# CAN_controller.net
KiCad netlist of a schematic drawn in Altium Designer
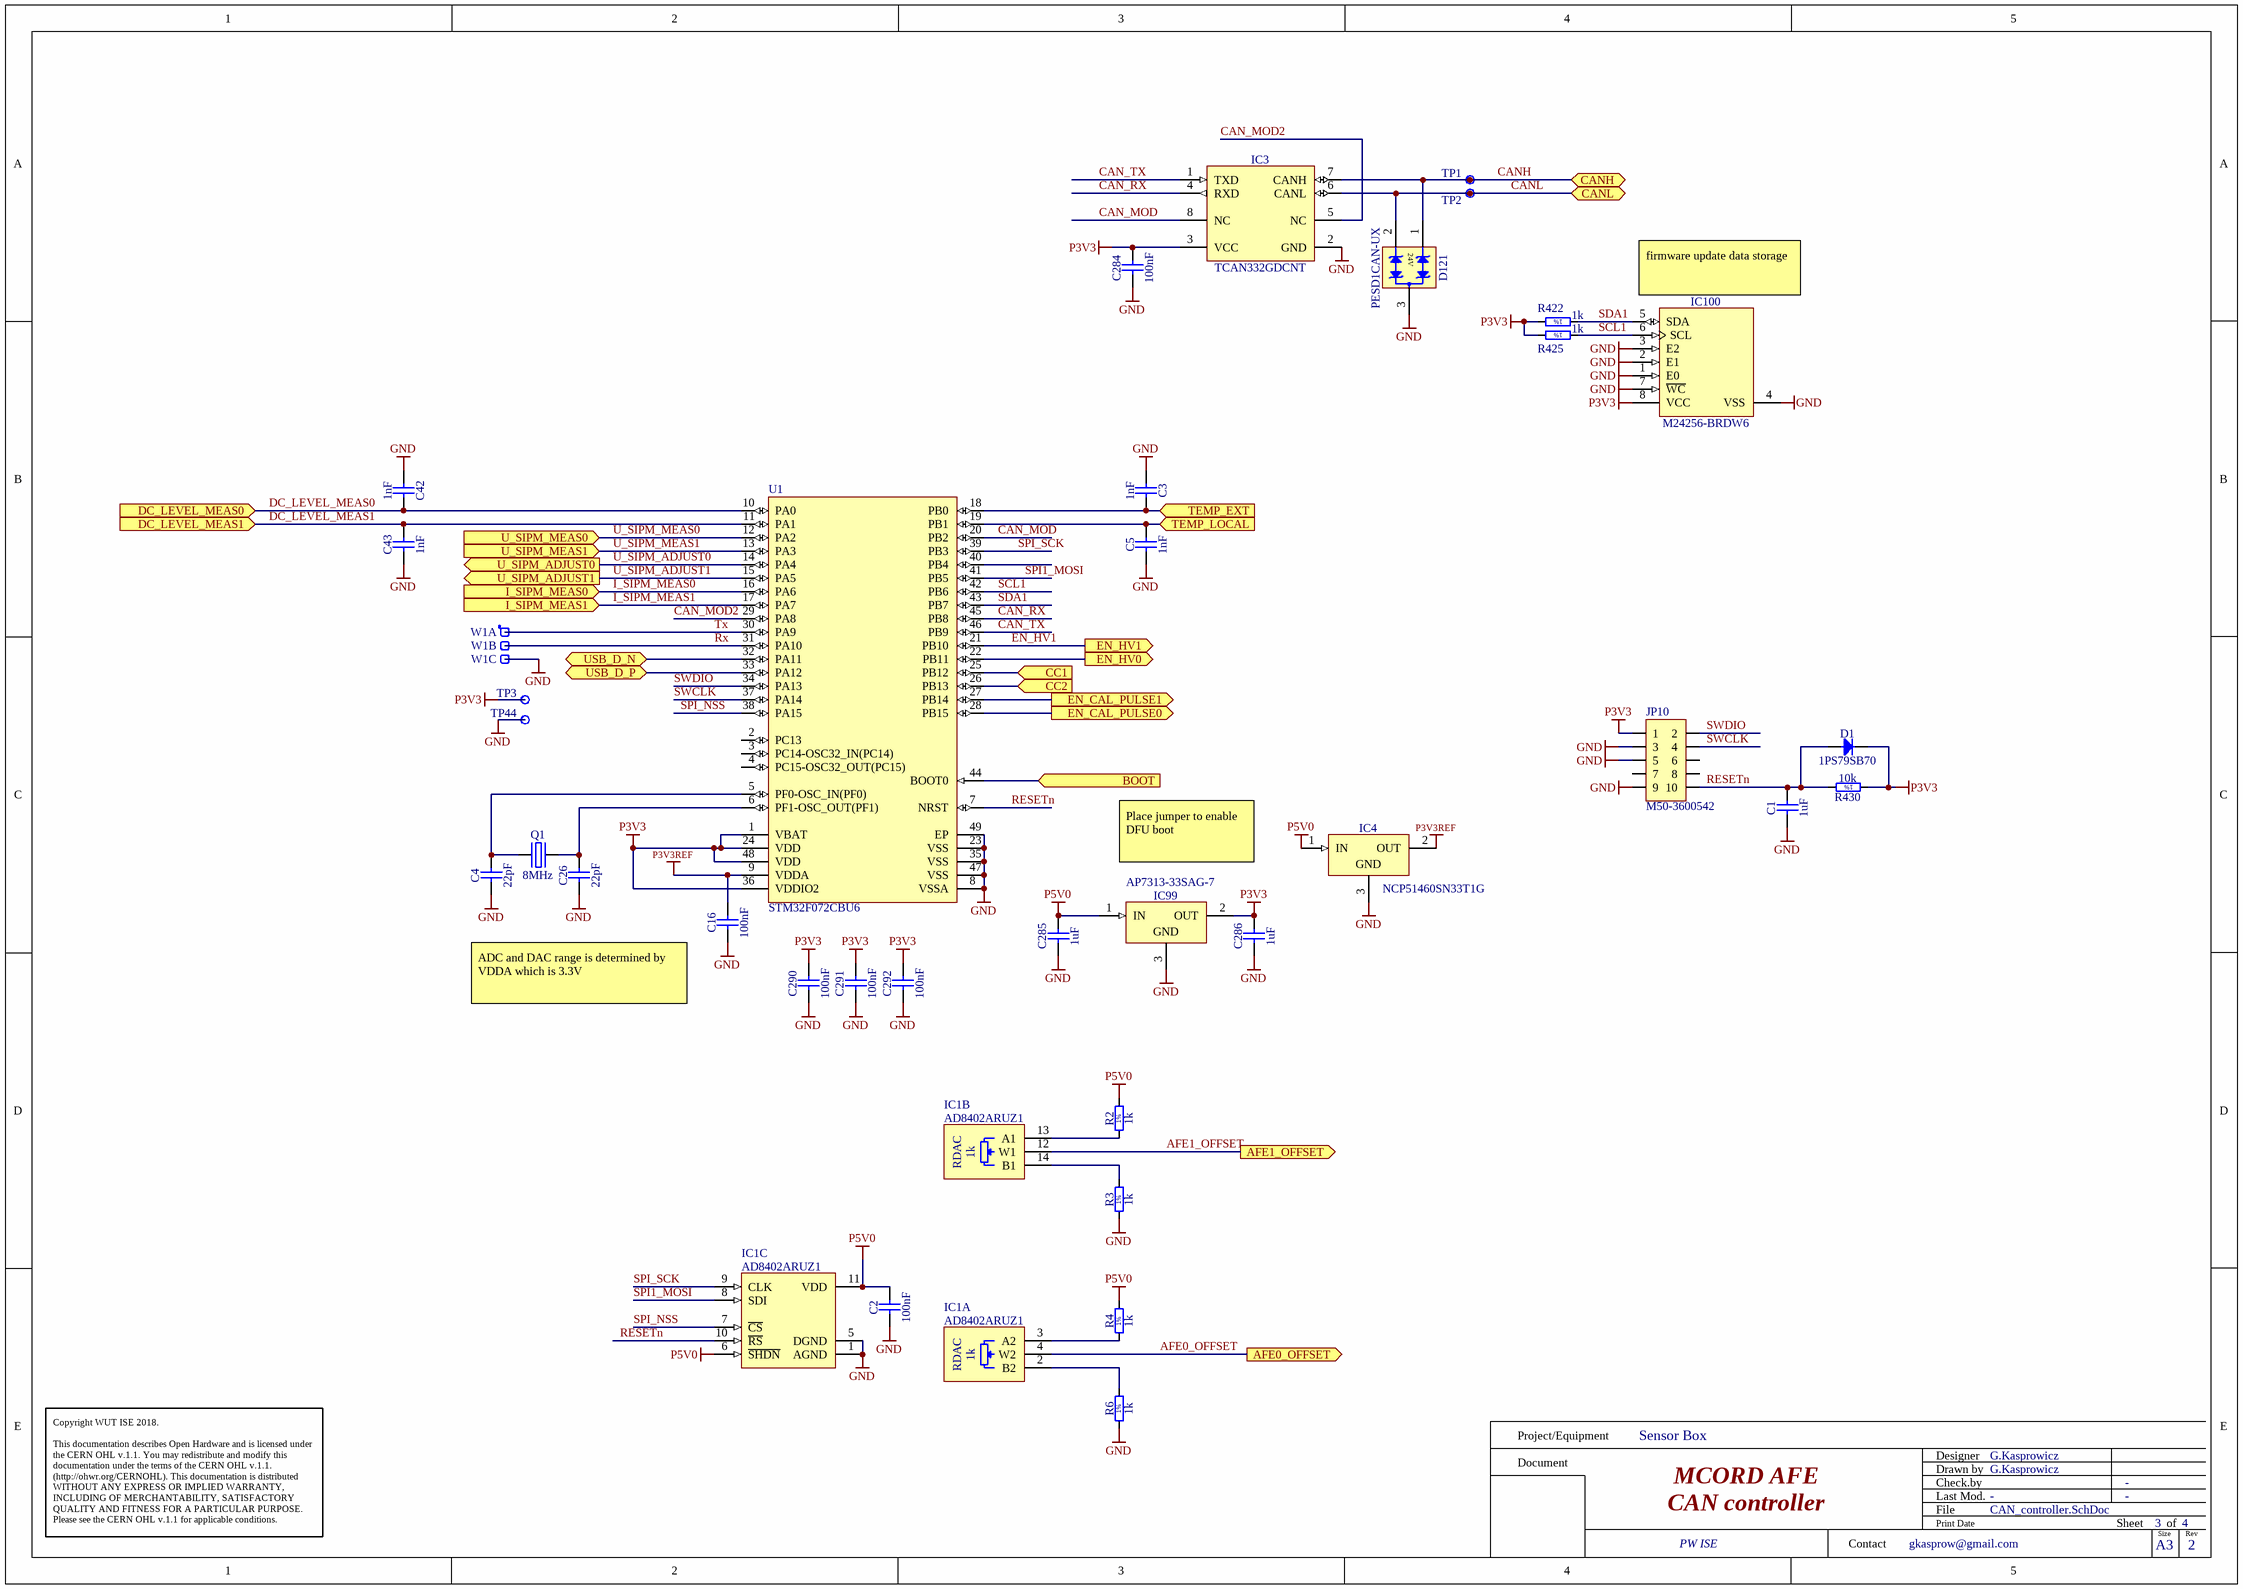
[diagram p0: CAN_controller.SchDoc]

(export (version "E")
  (design (tool "Eeschema 10.0.6"))
  (components
    (comp (ref "C1")
      (value "1uF")
      (footprint "CAPC1608X87N")
      (description "Non-polarised capacitor")
      (fields
        (field (name "PART NUMBER") "CC0603_1UF_16V_10%_X7R")
        (field (name "VOLTAGE") "16V")
        (field (name "AUTHOR") "CERN DEM JLC")
      )
      (libsource (lib "Capacitors") (part "Capacitor - non polarized"))
    )
    (comp (ref "C2")
      (value "100nF")
      (footprint "CAPC1005X55N")
      (description "Non-polarised capacitor")
      (fields
        (field (name "PART NUMBER") "CC0402_100NF_16V_10%_X7R")
        (field (name "VOLTAGE") "16V")
        (field (name "AUTHOR") "CERN DEM JLC")
      )
      (libsource (lib "Capacitors") (part "Capacitor - non polarized"))
    )
    (comp (ref "C3")
      (value "1nF")
      (footprint "CAPC1005X55N")
      (description "Non-polarised capacitor")
      (fields
        (field (name "PART NUMBER") "CC0402_1NF_50V_5%_C0G")
        (field (name "VOLTAGE") "50V")
        (field (name "AUTHOR") "CERN DEM BC")
      )
      (libsource (lib "Capacitors") (part "Capacitor - non polarized"))
    )
    (comp (ref "C4")
      (value "22pF")
      (footprint "CAPC1005X55N")
      (description "Non-polarised capacitor")
      (fields
        (field (name "PART NUMBER") "CC0402_22PF_50V_5%_C0G")
        (field (name "VOLTAGE") "50V")
        (field (name "AUTHOR") "CERN DEM JLC")
      )
      (libsource (lib "Capacitors") (part "Capacitor - non polarized"))
    )
    (comp (ref "C5")
      (value "1nF")
      (footprint "CAPC1005X55N")
      (description "Non-polarised capacitor")
      (fields
        (field (name "PART NUMBER") "CC0402_1NF_50V_5%_C0G")
        (field (name "VOLTAGE") "50V")
        (field (name "AUTHOR") "CERN DEM BC")
      )
      (libsource (lib "Capacitors") (part "Capacitor - non polarized"))
    )
    (comp (ref "C16")
      (value "100nF")
      (footprint "CAPC1005X55N")
      (description "Non-polarised capacitor")
      (fields
        (field (name "PART NUMBER") "CC0402_100NF_16V_10%_X7R")
        (field (name "VOLTAGE") "16V")
        (field (name "AUTHOR") "CERN DEM JLC")
      )
      (libsource (lib "Capacitors") (part "Capacitor - non polarized"))
    )
    (comp (ref "C26")
      (value "22pF")
      (footprint "CAPC1005X55N")
      (description "Non-polarised capacitor")
      (fields
        (field (name "PART NUMBER") "CC0402_22PF_50V_5%_C0G")
        (field (name "VOLTAGE") "50V")
        (field (name "AUTHOR") "CERN DEM JLC")
      )
      (libsource (lib "Capacitors") (part "Capacitor - non polarized"))
    )
    (comp (ref "C42")
      (value "1nF")
      (footprint "CAPC1005X55N")
      (description "Non-polarised capacitor")
      (fields
        (field (name "PART NUMBER") "CC0402_1NF_50V_5%_C0G")
        (field (name "VOLTAGE") "50V")
        (field (name "AUTHOR") "CERN DEM BC")
      )
      (libsource (lib "Capacitors") (part "Capacitor - non polarized"))
    )
    (comp (ref "C43")
      (value "1nF")
      (footprint "CAPC1005X55N")
      (description "Non-polarised capacitor")
      (fields
        (field (name "PART NUMBER") "CC0402_1NF_50V_5%_C0G")
        (field (name "VOLTAGE") "50V")
        (field (name "AUTHOR") "CERN DEM BC")
      )
      (libsource (lib "Capacitors") (part "Capacitor - non polarized"))
    )
    (comp (ref "C284")
      (value "100nF")
      (footprint "CAPC1005X55N")
      (description "Non-polarised capacitor")
      (fields
        (field (name "PART NUMBER") "CC0402_100NF_16V_10%_X7R")
        (field (name "VOLTAGE") "16V")
        (field (name "AUTHOR") "CERN DEM JLC")
      )
      (libsource (lib "Capacitors") (part "Capacitor - non polarized"))
    )
    (comp (ref "C285")
      (value "1uF")
      (footprint "CAPC1608X87N")
      (description "Non-polarised capacitor")
      (fields
        (field (name "PART NUMBER") "CC0603_1UF_16V_10%_X7R")
        (field (name "VOLTAGE") "16V")
        (field (name "AUTHOR") "CERN DEM JLC")
      )
      (libsource (lib "Capacitors") (part "Capacitor - non polarized"))
    )
    (comp (ref "C286")
      (value "1uF")
      (footprint "CAPC1608X87N")
      (description "Non-polarised capacitor")
      (fields
        (field (name "PART NUMBER") "CC0603_1UF_16V_10%_X7R")
        (field (name "VOLTAGE") "16V")
        (field (name "AUTHOR") "CERN DEM JLC")
      )
      (libsource (lib "Capacitors") (part "Capacitor - non polarized"))
    )
    (comp (ref "C290")
      (value "100nF")
      (footprint "CAPC1005X55N")
      (description "Non-polarised capacitor")
      (fields
        (field (name "PART NUMBER") "CC0402_100NF_16V_10%_X7R")
        (field (name "VOLTAGE") "16V")
        (field (name "AUTHOR") "CERN DEM JLC")
      )
      (libsource (lib "Capacitors") (part "Capacitor - non polarized"))
    )
    (comp (ref "C291")
      (value "100nF")
      (footprint "CAPC1005X55N")
      (description "Non-polarised capacitor")
      (fields
        (field (name "PART NUMBER") "CC0402_100NF_16V_10%_X7R")
        (field (name "VOLTAGE") "16V")
        (field (name "AUTHOR") "CERN DEM JLC")
      )
      (libsource (lib "Capacitors") (part "Capacitor - non polarized"))
    )
    (comp (ref "C292")
      (value "100nF")
      (footprint "CAPC1005X55N")
      (description "Non-polarised capacitor")
      (fields
        (field (name "PART NUMBER") "CC0402_100NF_16V_10%_X7R")
        (field (name "VOLTAGE") "16V")
        (field (name "AUTHOR") "CERN DEM JLC")
      )
      (libsource (lib "Capacitors") (part "Capacitor - non polarized"))
    )
    (comp (ref "D1")
      (value "1PS79SB70")
      (footprint "SODFL1608X65N")
      (description "Diode")
      (fields (field (name "VOLTAGE") "70V") (field (name "POWER") "70mA") (field (name "AUTHOR") "GK"))
      (libsource (lib "Diodes") (part "D_1PS79SB70"))
    )
    (comp (ref "D121")
      (value "PESD1CAN-UX")
      (footprint "SOT95P237X112-3N")
      (description "TVS Diode for CAN")
      (fields
        (field (name "VOLTAGE") "24V")
        (field (name "POWER") "400W")
        (field (name "AUTHOR") "CERN DEM JLC")
      )
      (libsource (lib "LIBRARY_SCH") (part "D_TVS_PESD1CAN"))
    )
    (comp (ref "IC1")
      (value "AD8402ARUZ1")
      (footprint "SOP65P640X120-14N")
      (description "2-Channel 1k Digital Potentiometer")
      (fields (field (name "MANUFACTURER") "ANALOG DEVICES") (field (name "AUTHOR") "GK"))
      (libsource (lib "ADC_DAC") (part "DAC_AD8402ARUZ1"))
    )
    (comp (ref "IC3")
      (value "TCAN332GDCNT")
      (footprint "SOT65P280X145-8N")
      (description "3.3V CAN Transceivers with CAN FD (Flexible Data Rate)")
      (fields (field (name "MANUFACTURER") "TEXAS INSTRUMENTS") (field (name "AUTHOR") "CERN DEM JLC"))
      (libsource (lib "ICs And Semiconductors") (part "TCAN332"))
    )
    (comp (ref "IC4")
      (value "NCP51460SN33T1G")
      (footprint "SOT95P240X110-3N")
      (description "3-Terminal Regulator 1=IN 2=OUT 3=GND")
      (fields (field (name "MANUFACTURER") "ON SEMICONDUCTOR") (field (name "AUTHOR") "CERN DEM MR"))
      (libsource (lib "ICs And Semiconductors") (part "REG3 1IN-2OUT-3GND"))
    )
    (comp (ref "IC99")
      (value "AP7313-33SAG-7")
      (footprint "SOT95P240X130-3N")
      (description "3-Terminal Regulator 1=IN 2=OUT 3=GND")
      (fields (field (name "MANUFACTURER") "DIODES INCORPORATED") (field (name "AUTHOR") "CERN DEM JLC"))
      (libsource (lib "ICs And Semiconductors") (part "REG3 1IN-2OUT-3GND"))
    )
    (comp (ref "IC100")
      (value "M24256-BRDW6")
      (footprint "SOP65P640X120-8N")
      (description "256-Kbit Serial I²C Bus EEPROM")
      (fields
        (field (name "PART NUMBER") "M24256-BRDW6P")
        (field (name "MANUFACTURER") "ST MICROELECTRONICS")
        (field (name "AUTHOR") "CERN DEM MR")
      )
      (libsource (lib "LIBRARY_SCH") (part "MEM_M24256-BRDW6P"))
    )
    (comp (ref "JP10")
      (value "M50-3600542")
      (footprint "PLHTD10S-TR-CV")
      (description "1.27 mm dual row goldpin (Harwin)")
      (libsource (lib "LIBRARY_SCH") (part "CON_2x5 1.27 SMT Male"))
    )
    (comp (ref "Q1")
      (value "8MHz")
      (footprint "XTAL_TXC_7A")
      (description "Quartz Crystal")
      (fields
        (field (name "PART NUMBER") "XTAL_8MHZ_TXC_7A-8.000MAAE-T")
        (field (name "MANUFACTURER") "TXC CORPORATION")
        (field (name "AUTHOR") "CERN DEM JLC")
      )
      (libsource (lib "ICs And Semiconductors") (part "Quartz Crystal"))
    )
    (comp (ref "R2")
      (value "1k")
      (footprint "RESC1005X40N")
      (description "Resistor - 1%")
      (fields
        (field (name "PART NUMBER") "R0402_1K_1%_0.0625W_100PPM")
        (field (name "POWER") "0.0625W")
        (field (name "AUTHOR") "CERN DEM JLC")
      )
      (libsource (lib "Resistors") (part "Resistor - 1%"))
    )
    (comp (ref "R3")
      (value "1k")
      (footprint "RESC1005X40N")
      (description "Resistor - 1%")
      (fields
        (field (name "PART NUMBER") "R0402_1K_1%_0.0625W_100PPM")
        (field (name "POWER") "0.0625W")
        (field (name "AUTHOR") "CERN DEM JLC")
      )
      (libsource (lib "Resistors") (part "Resistor - 1%"))
    )
    (comp (ref "R4")
      (value "1k")
      (footprint "RESC1005X40N")
      (description "Resistor - 1%")
      (fields
        (field (name "PART NUMBER") "R0402_1K_1%_0.0625W_100PPM")
        (field (name "POWER") "0.0625W")
        (field (name "AUTHOR") "CERN DEM JLC")
      )
      (libsource (lib "Resistors") (part "Resistor - 1%"))
    )
    (comp (ref "R6")
      (value "1k")
      (footprint "RESC1005X40N")
      (description "Resistor - 1%")
      (fields
        (field (name "PART NUMBER") "R0402_1K_1%_0.0625W_100PPM")
        (field (name "POWER") "0.0625W")
        (field (name "AUTHOR") "CERN DEM JLC")
      )
      (libsource (lib "Resistors") (part "Resistor - 1%"))
    )
    (comp (ref "R422")
      (value "1k")
      (footprint "RESC1005X40N")
      (description "Resistor - 1%")
      (fields
        (field (name "PART NUMBER") "R0402_1K_1%_0.0625W_100PPM")
        (field (name "POWER") "0.0625W")
        (field (name "AUTHOR") "CERN DEM JLC")
      )
      (libsource (lib "Resistors") (part "Resistor - 1%"))
    )
    (comp (ref "R425")
      (value "1k")
      (footprint "RESC1005X40N")
      (description "Resistor - 1%")
      (fields
        (field (name "PART NUMBER") "R0402_1K_1%_0.0625W_100PPM")
        (field (name "POWER") "0.0625W")
        (field (name "AUTHOR") "CERN DEM JLC")
      )
      (libsource (lib "Resistors") (part "Resistor - 1%"))
    )
    (comp (ref "R430")
      (value "10k")
      (footprint "RESC1005X40N")
      (description "Resistor - 1%")
      (fields
        (field (name "PART NUMBER") "R0402_10K_1%_0.0625W_100PPM")
        (field (name "POWER") "0.0625W")
        (field (name "AUTHOR") "CERN DEM JLC")
      )
      (libsource (lib "Resistors") (part "Resistor - 1%"))
    )
    (comp (ref "TP1")
      (value "Test Point")
      (footprint "TPS127")
      (fields (field (name "PART NUMBER") "SMD_PAD_1.27X1.27MM") (field (name "AUTHOR") "CERN DEM JLC"))
      (libsource (lib "Eletro-mechanical") (part "Test Point"))
    )
    (comp (ref "TP2")
      (value "Test Point")
      (footprint "TPS127")
      (fields (field (name "PART NUMBER") "SMD_PAD_1.27X1.27MM") (field (name "AUTHOR") "CERN DEM JLC"))
      (libsource (lib "Eletro-mechanical") (part "Test Point"))
    )
    (comp (ref "TP3")
      (value "Test Point")
      (footprint "TPS127")
      (fields (field (name "PART NUMBER") "SMD_PAD_1.27X1.27MM") (field (name "AUTHOR") "CERN DEM JLC"))
      (libsource (lib "Eletro-mechanical") (part "Test Point"))
    )
    (comp (ref "TP44")
      (value "Test Point")
      (footprint "TPS127")
      (fields (field (name "PART NUMBER") "SMD_PAD_1.27X1.27MM") (field (name "AUTHOR") "CERN DEM JLC"))
      (libsource (lib "Eletro-mechanical") (part "Test Point"))
    )
    (comp (ref "U1")
      (value "STM32F072CBU6")
      (footprint "STM-UFQFPN48_L")
      (fields (field (name "MANUFACTURER") "STMicroelectronics"))
      (libsource (lib "Altium Content Vault") (part "MC-ARM-STM32F072-UFQFPN48"))
    )
    (comp (ref "W1")
      (value "Header 3")
      (footprint "SAMTEC_HTSW-103-23-L-S")
      (description "3 Mini Wire-Wrap Contact Strip Header")
      (fields
        (field (name "PART NUMBER") "SAMTEC_HTSW-103-23-L-S")
        (field (name "MANUFACTURER") "SAMTEC")
        (field (name "AUTHOR") "CERN DEM JLC")
      )
      (libsource (lib "Connectors") (part "Wire-Wrap Contact x3"))
    )
  )
  (nets
    (net (code "1") (name "/AFE0_OFFSET") (class "Default")
      (node (ref "IC1") (pin "4") (pinfunction "W2_4") (pintype "passive"))
    )
    (net (code "2") (name "/AFE1_OFFSET") (class "Default")
      (node (ref "IC1") (pin "12") (pinfunction "W1_12") (pintype "passive"))
    )
    (net (code "3") (name "/BOOT") (class "Default")
      (node (ref "U1") (pin "44") (pinfunction "BOOT0_44") (pintype "input"))
    )
    (net (code "4") (name "/CANH") (class "Default")
      (node (ref "D121") (pin "1") (pinfunction "I/O1_1") (pintype "passive"))
      (node (ref "IC3") (pin "7") (pinfunction "CANH_7") (pintype "bidirectional"))
      (node (ref "TP1") (pin "1") (pinfunction "1_1") (pintype "bidirectional"))
    )
    (net (code "5") (name "/CANL") (class "Default")
      (node (ref "D121") (pin "2") (pinfunction "I/O2_2") (pintype "passive"))
      (node (ref "IC3") (pin "6") (pinfunction "CANL_6") (pintype "bidirectional"))
      (node (ref "TP2") (pin "1") (pinfunction "1_1") (pintype "bidirectional"))
    )
    (net (code "6") (name "/CAN_MOD") (class "Default")
      (node (ref "IC3") (pin "8") (pinfunction "NC_8") (pintype "passive"))
      (node (ref "U1") (pin "20") (pinfunction "PB2_20") (pintype "bidirectional"))
    )
    (net (code "7") (name "/CAN_MOD2") (class "Default")
      (node (ref "IC3") (pin "5") (pinfunction "NC_5") (pintype "passive"))
      (node (ref "U1") (pin "29") (pinfunction "PA8_29") (pintype "bidirectional"))
    )
    (net (code "8") (name "/CAN_RX") (class "Default")
      (node (ref "IC3") (pin "4") (pinfunction "RXD_4") (pintype "output"))
      (node (ref "U1") (pin "45") (pinfunction "PB8_45") (pintype "bidirectional"))
    )
    (net (code "9") (name "/CAN_TX") (class "Default")
      (node (ref "IC3") (pin "1") (pinfunction "TXD_1") (pintype "input"))
      (node (ref "U1") (pin "46") (pinfunction "PB9_46") (pintype "bidirectional"))
    )
    (net (code "10") (name "/CC1") (class "Default")
      (node (ref "U1") (pin "25") (pinfunction "PB12_25") (pintype "bidirectional"))
    )
    (net (code "11") (name "/CC2") (class "Default")
      (node (ref "U1") (pin "26") (pinfunction "PB13_26") (pintype "bidirectional"))
    )
    (net (code "12") (name "/DC_LEVEL_MEAS0") (class "Default")
      (node (ref "C42") (pin "2") (pinfunction "2_2") (pintype "passive"))
      (node (ref "U1") (pin "10") (pinfunction "PA0_10") (pintype "bidirectional"))
    )
    (net (code "13") (name "/DC_LEVEL_MEAS1") (class "Default")
      (node (ref "C43") (pin "2") (pinfunction "2_2") (pintype "passive"))
      (node (ref "U1") (pin "11") (pinfunction "PA1_11") (pintype "bidirectional"))
    )
    (net (code "14") (name "/EN_CAL_PULSE0") (class "Default")
      (node (ref "U1") (pin "28") (pinfunction "PB15_28") (pintype "bidirectional"))
    )
    (net (code "15") (name "/EN_CAL_PULSE1") (class "Default")
      (node (ref "U1") (pin "27") (pinfunction "PB14_27") (pintype "bidirectional"))
    )
    (net (code "16") (name "/EN_HV0") (class "Default")
      (node (ref "U1") (pin "22") (pinfunction "PB11_22") (pintype "bidirectional"))
    )
    (net (code "17") (name "/EN_HV1") (class "Default")
      (node (ref "U1") (pin "21") (pinfunction "PB10_21") (pintype "bidirectional"))
    )
    (net (code "18") (name "/I_SIPM_MEAS0") (class "Default")
      (node (ref "U1") (pin "16") (pinfunction "PA6_16") (pintype "bidirectional"))
    )
    (net (code "19") (name "/I_SIPM_MEAS1") (class "Default")
      (node (ref "U1") (pin "17") (pinfunction "PA7_17") (pintype "bidirectional"))
    )
    (net (code "20") (name "/RESETn") (class "Default")
      (node (ref "C1") (pin "2") (pinfunction "2_2") (pintype "passive"))
      (node (ref "D1") (pin "2") (pinfunction "A_2") (pintype "passive"))
      (node (ref "IC1") (pin "10") (pinfunction "~{RS}_10") (pintype "input"))
      (node (ref "JP10") (pin "10") (pinfunction "10_10") (pintype "passive"))
      (node (ref "R430") (pin "2") (pinfunction "2_2") (pintype "passive"))
      (node (ref "U1") (pin "7") (pinfunction "NRST_7") (pintype "bidirectional"))
    )
    (net (code "21") (name "/Rx") (class "Default")
      (node (ref "U1") (pin "31") (pinfunction "PA10_31") (pintype "bidirectional"))
      (node (ref "W1") (pin "2") (pinfunction "2_2") (pintype "bidirectional"))
    )
    (net (code "22") (name "/SCL1") (class "Default")
      (node (ref "IC100") (pin "6") (pinfunction "SCL_6") (pintype "input"))
      (node (ref "R425") (pin "1") (pinfunction "1_1") (pintype "passive"))
      (node (ref "U1") (pin "42") (pinfunction "PB6_42") (pintype "bidirectional"))
    )
    (net (code "23") (name "/SDA1") (class "Default")
      (node (ref "IC100") (pin "5") (pinfunction "SDA_5") (pintype "bidirectional"))
      (node (ref "R422") (pin "1") (pinfunction "1_1") (pintype "passive"))
      (node (ref "U1") (pin "43") (pinfunction "PB7_43") (pintype "bidirectional"))
    )
    (net (code "24") (name "/SPI1_MOSI") (class "Default")
      (node (ref "IC1") (pin "8") (pinfunction "SDI_8") (pintype "input"))
      (node (ref "U1") (pin "41") (pinfunction "PB5_41") (pintype "bidirectional"))
    )
    (net (code "25") (name "/SPI_NSS") (class "Default")
      (node (ref "IC1") (pin "7") (pinfunction "~{CS}_7") (pintype "input"))
      (node (ref "U1") (pin "38") (pinfunction "PA15_38") (pintype "bidirectional"))
    )
    (net (code "26") (name "/SPI_SCK") (class "Default")
      (node (ref "IC1") (pin "9") (pinfunction "CLK_9") (pintype "input"))
      (node (ref "U1") (pin "39") (pinfunction "PB3_39") (pintype "bidirectional"))
    )
    (net (code "27") (name "/SWCLK") (class "Default")
      (node (ref "JP10") (pin "4") (pinfunction "4_4") (pintype "passive"))
      (node (ref "U1") (pin "37") (pinfunction "PA14_37") (pintype "bidirectional"))
    )
    (net (code "28") (name "/SWDIO") (class "Default")
      (node (ref "JP10") (pin "2") (pinfunction "2_2") (pintype "passive"))
      (node (ref "U1") (pin "34") (pinfunction "PA13_34") (pintype "bidirectional"))
    )
    (net (code "29") (name "/TEMP_EXT") (class "Default")
      (node (ref "C3") (pin "2") (pinfunction "2_2") (pintype "passive"))
      (node (ref "U1") (pin "18") (pinfunction "PB0_18") (pintype "bidirectional"))
    )
    (net (code "30") (name "/TEMP_LOCAL") (class "Default")
      (node (ref "C5") (pin "2") (pinfunction "2_2") (pintype "passive"))
      (node (ref "U1") (pin "19") (pinfunction "PB1_19") (pintype "bidirectional"))
    )
    (net (code "31") (name "/Tx") (class "Default")
      (node (ref "U1") (pin "30") (pinfunction "PA9_30") (pintype "bidirectional"))
      (node (ref "W1") (pin "1") (pinfunction "1_1") (pintype "bidirectional"))
    )
    (net (code "32") (name "/USB_D_N") (class "Default")
      (node (ref "U1") (pin "32") (pinfunction "PA11_32") (pintype "bidirectional"))
    )
    (net (code "33") (name "/USB_D_P") (class "Default")
      (node (ref "U1") (pin "33") (pinfunction "PA12_33") (pintype "bidirectional"))
    )
    (net (code "34") (name "/U_SIPM_ADJUST0") (class "Default")
      (node (ref "U1") (pin "14") (pinfunction "PA4_14") (pintype "bidirectional"))
    )
    (net (code "35") (name "/U_SIPM_ADJUST1") (class "Default")
      (node (ref "U1") (pin "15") (pinfunction "PA5_15") (pintype "bidirectional"))
    )
    (net (code "36") (name "/U_SIPM_MEAS0") (class "Default")
      (node (ref "U1") (pin "12") (pinfunction "PA2_12") (pintype "bidirectional"))
    )
    (net (code "37") (name "/U_SIPM_MEAS1") (class "Default")
      (node (ref "U1") (pin "13") (pinfunction "PA3_13") (pintype "bidirectional"))
    )
    (net (code "38") (name "GND") (class "Default")
      (node (ref "C1") (pin "1") (pinfunction "1_1") (pintype "passive"))
      (node (ref "C16") (pin "1") (pinfunction "1_1") (pintype "passive"))
      (node (ref "C2") (pin "1") (pinfunction "1_1") (pintype "passive"))
      (node (ref "C26") (pin "1") (pinfunction "1_1") (pintype "passive"))
      (node (ref "C284") (pin "1") (pinfunction "1_1") (pintype "passive"))
      (node (ref "C285") (pin "1") (pinfunction "1_1") (pintype "passive"))
      (node (ref "C286") (pin "1") (pinfunction "1_1") (pintype "passive"))
      (node (ref "C290") (pin "1") (pinfunction "1_1") (pintype "passive"))
      (node (ref "C291") (pin "1") (pinfunction "1_1") (pintype "passive"))
      (node (ref "C292") (pin "1") (pinfunction "1_1") (pintype "passive"))
      (node (ref "C3") (pin "1") (pinfunction "1_1") (pintype "passive"))
      (node (ref "C4") (pin "1") (pinfunction "1_1") (pintype "passive"))
      (node (ref "C42") (pin "1") (pinfunction "1_1") (pintype "passive"))
      (node (ref "C43") (pin "1") (pinfunction "1_1") (pintype "passive"))
      (node (ref "C5") (pin "1") (pinfunction "1_1") (pintype "passive"))
      (node (ref "D121") (pin "3") (pinfunction "GND_3") (pintype "passive"))
      (node (ref "IC1") (pin "1") (pinfunction "AGND_1") (pintype "power_in"))
      (node (ref "IC1") (pin "5") (pinfunction "DGND_5") (pintype "power_in"))
      (node (ref "IC100") (pin "1") (pinfunction "E0_1") (pintype "input"))
      (node (ref "IC100") (pin "2") (pinfunction "E1_2") (pintype "input"))
      (node (ref "IC100") (pin "3") (pinfunction "E2_3") (pintype "input"))
      (node (ref "IC100") (pin "4") (pinfunction "VSS_4") (pintype "power_in"))
      (node (ref "IC100") (pin "7") (pinfunction "~{WC}_7") (pintype "input"))
      (node (ref "IC3") (pin "2") (pinfunction "GND_2") (pintype "power_in"))
      (node (ref "IC4") (pin "3") (pinfunction "GND_3") (pintype "power_in"))
      (node (ref "IC99") (pin "3") (pinfunction "GND_3") (pintype "power_in"))
      (node (ref "JP10") (pin "3") (pinfunction "3_3") (pintype "passive"))
      (node (ref "JP10") (pin "5") (pinfunction "5_5") (pintype "passive"))
      (node (ref "JP10") (pin "9") (pinfunction "9_9") (pintype "passive"))
      (node (ref "R3") (pin "1") (pinfunction "1_1") (pintype "passive"))
      (node (ref "R6") (pin "1") (pinfunction "1_1") (pintype "passive"))
      (node (ref "TP44") (pin "1") (pinfunction "1_1") (pintype "bidirectional"))
      (node (ref "U1") (pin "23") (pinfunction "VSS_23") (pintype "power_in"))
      (node (ref "U1") (pin "35") (pinfunction "VSS_35") (pintype "power_in"))
      (node (ref "U1") (pin "47") (pinfunction "VSS_47") (pintype "power_in"))
      (node (ref "U1") (pin "49") (pinfunction "EP_49") (pintype "power_in"))
      (node (ref "U1") (pin "8") (pinfunction "VSSA_8") (pintype "power_in"))
      (node (ref "W1") (pin "3") (pinfunction "3_3") (pintype "bidirectional"))
    )
    (net (code "39") (name "Net-(IC1A-A2)") (class "Default")
      (node (ref "IC1") (pin "3") (pinfunction "A2_3") (pintype "passive"))
      (node (ref "R4") (pin "1") (pinfunction "1_1") (pintype "passive"))
    )
    (net (code "40") (name "Net-(IC1A-B2)") (class "Default")
      (node (ref "IC1") (pin "2") (pinfunction "B2_2") (pintype "passive"))
      (node (ref "R6") (pin "2") (pinfunction "2_2") (pintype "passive"))
    )
    (net (code "41") (name "Net-(IC1B-A1)") (class "Default")
      (node (ref "IC1") (pin "13") (pinfunction "A1_13") (pintype "passive"))
      (node (ref "R2") (pin "1") (pinfunction "1_1") (pintype "passive"))
    )
    (net (code "42") (name "Net-(IC1B-B1)") (class "Default")
      (node (ref "IC1") (pin "14") (pinfunction "B1_14") (pintype "passive"))
      (node (ref "R3") (pin "2") (pinfunction "2_2") (pintype "passive"))
    )
    (net (code "43") (name "Net-(Q1-OSC1)") (class "Default")
      (node (ref "C4") (pin "2") (pinfunction "2_2") (pintype "passive"))
      (node (ref "Q1") (pin "1") (pinfunction "OSC1_1") (pintype "passive"))
      (node (ref "U1") (pin "5") (pinfunction "PF0-OSC_IN(PF0)_5") (pintype "bidirectional"))
    )
    (net (code "44") (name "Net-(Q1-OSC2)") (class "Default")
      (node (ref "C26") (pin "2") (pinfunction "2_2") (pintype "passive"))
      (node (ref "Q1") (pin "2") (pinfunction "OSC2_2") (pintype "passive"))
      (node (ref "U1") (pin "6") (pinfunction "PF1-OSC_OUT(PF1)_6") (pintype "bidirectional"))
    )
    (net (code "45") (name "P3V3") (class "Default")
      (node (ref "C284") (pin "2") (pinfunction "2_2") (pintype "passive"))
      (node (ref "C286") (pin "2") (pinfunction "2_2") (pintype "passive"))
      (node (ref "C290") (pin "2") (pinfunction "2_2") (pintype "passive"))
      (node (ref "C291") (pin "2") (pinfunction "2_2") (pintype "passive"))
      (node (ref "C292") (pin "2") (pinfunction "2_2") (pintype "passive"))
      (node (ref "D1") (pin "1") (pinfunction "C_1") (pintype "passive"))
      (node (ref "IC100") (pin "8") (pinfunction "VCC_8") (pintype "power_in"))
      (node (ref "IC3") (pin "3") (pinfunction "VCC_3") (pintype "power_in"))
      (node (ref "IC99") (pin "2") (pinfunction "OUT_2") (pintype "power_in"))
      (node (ref "JP10") (pin "1") (pinfunction "1_1") (pintype "passive"))
      (node (ref "R422") (pin "2") (pinfunction "2_2") (pintype "passive"))
      (node (ref "R425") (pin "2") (pinfunction "2_2") (pintype "passive"))
      (node (ref "R430") (pin "1") (pinfunction "1_1") (pintype "passive"))
      (node (ref "TP3") (pin "1") (pinfunction "1_1") (pintype "bidirectional"))
      (node (ref "U1") (pin "1") (pinfunction "VBAT_1") (pintype "power_in"))
      (node (ref "U1") (pin "24") (pinfunction "VDD_24") (pintype "power_in"))
      (node (ref "U1") (pin "36") (pinfunction "VDDIO2_36") (pintype "power_in"))
      (node (ref "U1") (pin "48") (pinfunction "VDD_48") (pintype "power_in"))
    )
    (net (code "46") (name "P3V3REF") (class "Default")
      (node (ref "C16") (pin "2") (pinfunction "2_2") (pintype "passive"))
      (node (ref "IC4") (pin "2") (pinfunction "OUT_2") (pintype "power_in"))
      (node (ref "U1") (pin "9") (pinfunction "VDDA_9") (pintype "power_in"))
    )
    (net (code "47") (name "P5V0") (class "Default")
      (node (ref "C2") (pin "2") (pinfunction "2_2") (pintype "passive"))
      (node (ref "C285") (pin "2") (pinfunction "2_2") (pintype "passive"))
      (node (ref "IC1") (pin "11") (pinfunction "VDD_11") (pintype "power_in"))
      (node (ref "IC1") (pin "6") (pinfunction "~{SHDN}_6") (pintype "input"))
      (node (ref "IC4") (pin "1") (pinfunction "IN_1") (pintype "input"))
      (node (ref "IC99") (pin "1") (pinfunction "IN_1") (pintype "input"))
      (node (ref "R2") (pin "2") (pinfunction "2_2") (pintype "passive"))
      (node (ref "R4") (pin "2") (pinfunction "2_2") (pintype "passive"))
    )
    (net (code "48") (name "unconnected-(JP10-Pad6)") (class "Default")
      (node (ref "JP10") (pin "6") (pinfunction "6_6") (pintype "passive"))
    )
    (net (code "49") (name "unconnected-(JP10-Pad7)") (class "Default")
      (node (ref "JP10") (pin "7") (pinfunction "7_7") (pintype "passive"))
    )
    (net (code "50") (name "unconnected-(JP10-Pad8)") (class "Default")
      (node (ref "JP10") (pin "8") (pinfunction "8_8") (pintype "passive"))
    )
    (net (code "51") (name "unconnected-(U1-PB4-Pad40)") (class "Default")
      (node (ref "U1") (pin "40") (pinfunction "PB4_40") (pintype "bidirectional"))
    )
    (net (code "52") (name "unconnected-(U1-PC13-Pad2)") (class "Default")
      (node (ref "U1") (pin "2") (pinfunction "PC13_2") (pintype "bidirectional"))
    )
    (net (code "53") (name "unconnected-(U1-PC14-OSC32_IN(PC14)-Pad3)") (class "Default")
      (node (ref "U1") (pin "3") (pinfunction "PC14-OSC32_IN(PC14)_3") (pintype "bidirectional"))
    )
    (net (code "54") (name "unconnected-(U1-PC15-OSC32_OUT(PC15)-Pad4)") (class "Default")
      (node (ref "U1") (pin "4") (pinfunction "PC15-OSC32_OUT(PC15)_4") (pintype "bidirectional"))
    )
  )
)
